# EFUSE_AND_REGULATOR.net
KiCad netlist of a schematic drawn in Altium Designer
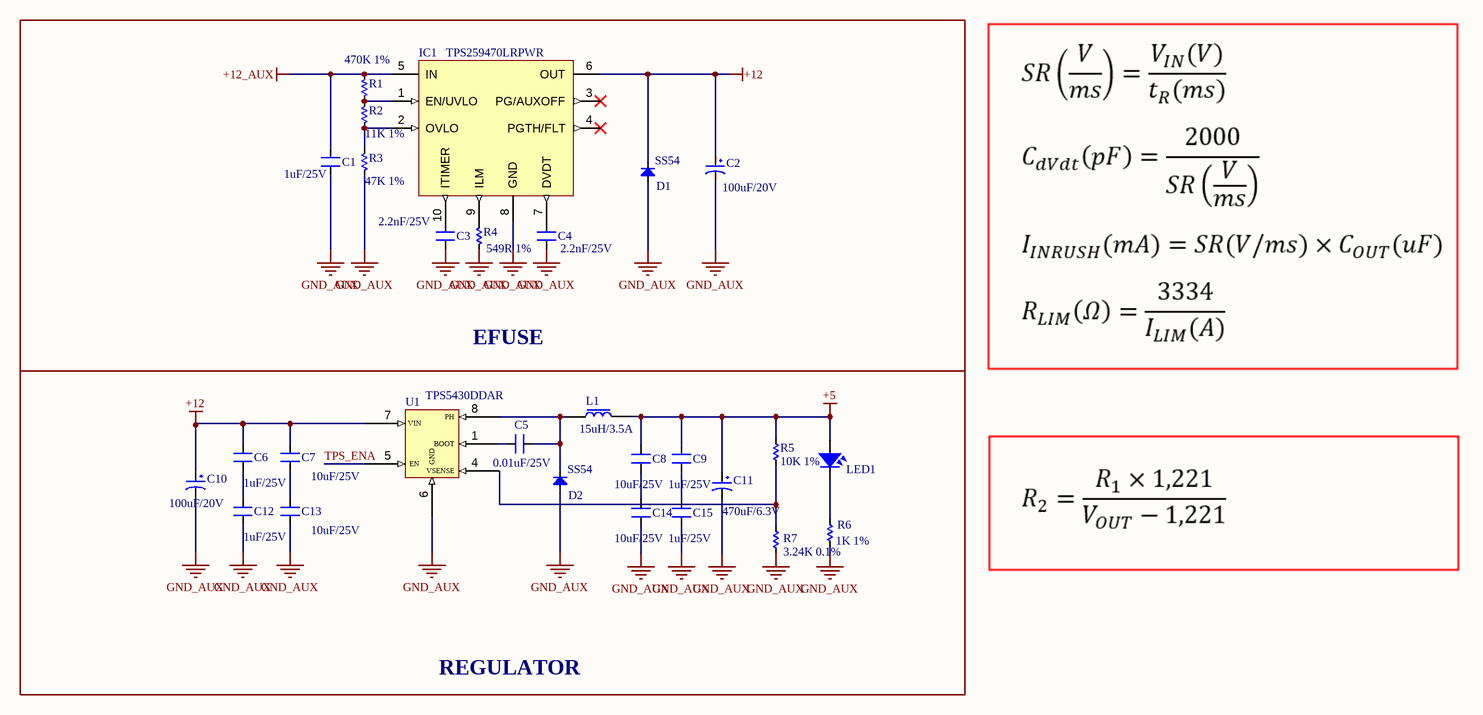
[diagram p0: EFUSE_AND_REGULATOR.SchDoc]

(export (version "E")
  (design (tool "Eeschema 10.0.6"))
  (components
    (comp (ref "C1")
      (value "1uF/25V")
      (footprint "SM-0603")
      (description "0603")
      (libsource (lib "Capacitors") (part "CM"))
    )
    (comp (ref "C2")
      (value "100uF/20V")
      (footprint "tu tantalum smd7343")
      (description "TAJD107K020RNJ")
      (libsource (lib "Altium_Lib_by_KhueNguyenCreator") (part "Tu tantalum 100uF 25V SMD7343"))
    )
    (comp (ref "C3")
      (value "2.2nF/25V")
      (footprint "SM-0603")
      (description "0603")
      (libsource (lib "Capacitors") (part "CM"))
    )
    (comp (ref "C4")
      (value "2.2nF/25V")
      (footprint "SM-0603")
      (description "0603")
      (libsource (lib "Capacitors") (part "CM"))
    )
    (comp (ref "C5")
      (value "0.01uF/25V")
      (footprint "SM-0603")
      (description "0603")
      (libsource (lib "Capacitors") (part "CM"))
    )
    (comp (ref "C6")
      (value "1uF/25V")
      (footprint "SM-0603")
      (description "0603")
      (libsource (lib "Capacitors") (part "CM"))
    )
    (comp (ref "C7")
      (value "10uF/25V")
      (footprint "SM-0603")
      (description "0603")
      (libsource (lib "Capacitors") (part "CM"))
    )
    (comp (ref "C8")
      (value "10uF/25V")
      (footprint "SM-0603")
      (description "0603")
      (libsource (lib "Capacitors") (part "CM"))
    )
    (comp (ref "C9")
      (value "1uF/25V")
      (footprint "SM-0603")
      (description "0603")
      (libsource (lib "Capacitors") (part "CM"))
    )
    (comp (ref "C10")
      (value "100uF/20V")
      (footprint "tu tantalum smd7343")
      (description "TAJD107K020RNJ")
      (libsource (lib "Altium_Lib_by_KhueNguyenCreator") (part "Tu tantalum 100uF 25V SMD7343"))
    )
    (comp (ref "C11")
      (value "470uF/6.3V")
      (footprint "tu tantalum smd7343")
      (description "TAJD477K006RNJ")
      (libsource (lib "Altium_Lib_by_KhueNguyenCreator") (part "Tu tantalum 100uF 25V SMD7343"))
    )
    (comp (ref "C12")
      (value "1uF/25V")
      (footprint "SM-0603")
      (description "0603")
      (libsource (lib "Capacitors") (part "CM"))
    )
    (comp (ref "C13")
      (value "10uF/25V")
      (footprint "SM-0603")
      (description "0603")
      (libsource (lib "Capacitors") (part "CM"))
    )
    (comp (ref "C14")
      (value "10uF/25V")
      (footprint "SM-0603")
      (description "0603")
      (libsource (lib "Capacitors") (part "CM"))
    )
    (comp (ref "C15")
      (value "1uF/25V")
      (footprint "SM-0603")
      (description "0603")
      (libsource (lib "Capacitors") (part "CM"))
    )
    (comp (ref "D1")
      (value "SS54")
      (footprint "DIO-SMD-A")
      (description "DIODE SCHOTTKY 40V 5A SMA")
      (fields (field (name "PUBLISHER") "Altium Limited"))
      (libsource (lib "Library") (part "Diode SMD"))
    )
    (comp (ref "D2")
      (value "SS54")
      (footprint "DIO-SMD-A")
      (description "DIODE SCHOTTKY 40V 5A SMA")
      (fields (field (name "PUBLISHER") "Altium Limited"))
      (libsource (lib "Library") (part "Diode SMD"))
    )
    (comp (ref "IC1")
      (value "TPS259470LRPWR")
      (footprint "TPS259470")
      (description "P/N: TPS259470LRPWR")
      (libsource (lib "Library") (part "TPS259470"))
    )
    (comp (ref "L1")
      (value "15uH/3.5A")
      (footprint "SRP7050TA")
      (description "SRP7050TA-150M")
      (libsource (lib "Library") (part "INDUCTOR"))
    )
    (comp (ref "LED1") (value "LED") (footprint "REDLED_0603") (libsource (lib "Library") (part "LED SMD")))
    (comp (ref "R1")
      (value "470K 1%")
      (footprint "RES-SMD-0603")
      (description "0603")
      (fields
        (field (name "MANUFACTURER") "Generic Components")
        (field (name "PUBLISHER") "Altium Hobart Technology Centre")
      )
      (libsource (lib "Library") (part "Res-SMD"))
    )
    (comp (ref "R2")
      (value "11K 1%")
      (footprint "RES-SMD-0603")
      (description "0603")
      (fields
        (field (name "MANUFACTURER") "Generic Components")
        (field (name "PUBLISHER") "Altium Hobart Technology Centre")
      )
      (libsource (lib "Library") (part "Res-SMD"))
    )
    (comp (ref "R3")
      (value "47K 1%")
      (footprint "RES-SMD-0603")
      (description "0603")
      (fields
        (field (name "MANUFACTURER") "Generic Components")
        (field (name "PUBLISHER") "Altium Hobart Technology Centre")
      )
      (libsource (lib "Library") (part "Res-SMD"))
    )
    (comp (ref "R4")
      (value "549R 1%")
      (footprint "RES-SMD-0603")
      (description "0603")
      (fields
        (field (name "MANUFACTURER") "Generic Components")
        (field (name "PUBLISHER") "Altium Hobart Technology Centre")
      )
      (libsource (lib "Library") (part "Res-SMD"))
    )
    (comp (ref "R5")
      (value "10K 1%")
      (footprint "RES-SMD-0603")
      (description "0603")
      (fields
        (field (name "MANUFACTURER") "Generic Components")
        (field (name "PUBLISHER") "Altium Hobart Technology Centre")
      )
      (libsource (lib "Library") (part "Res-SMD"))
    )
    (comp (ref "R6")
      (value "1K 1%")
      (footprint "RES-SMD-0603")
      (description "0603")
      (fields
        (field (name "MANUFACTURER") "Generic Components")
        (field (name "PUBLISHER") "Altium Hobart Technology Centre")
      )
      (libsource (lib "Library") (part "Res-SMD"))
    )
    (comp (ref "R7")
      (value "3.24K 0.1%")
      (footprint "RES-SMD-0603")
      (description "ERA-3AEB3241V")
      (fields
        (field (name "MANUFACTURER") "Generic Components")
        (field (name "PUBLISHER") "Altium Hobart Technology Centre")
      )
      (libsource (lib "Library") (part "Res-SMD"))
    )
    (comp (ref "U1")
      (value "TPS5430DDAR")
      (footprint "HSOP8")
      (description "8SOP")
      (libsource (lib "Library") (part "TPS543X"))
    )
  )
  (nets
    (net (code "1") (name "+5") (class "Default")
      (node (ref "C11") (pin "1") (pinfunction "1_1") (pintype "passive"))
      (node (ref "C8") (pin "1") (pinfunction "1_1") (pintype "passive"))
      (node (ref "C9") (pin "1") (pinfunction "1_1") (pintype "passive"))
      (node (ref "L1") (pin "2") (pintype "power_in"))
      (node (ref "LED1") (pin "1") (pinfunction "1_1") (pintype "passive"))
      (node (ref "R5") (pin "2") (pinfunction "2_2") (pintype "passive"))
    )
    (net (code "2") (name "+12") (class "Default")
      (node (ref "C10") (pin "1") (pinfunction "1_1") (pintype "passive"))
      (node (ref "C2") (pin "1") (pinfunction "1_1") (pintype "passive"))
      (node (ref "C6") (pin "1") (pinfunction "1_1") (pintype "passive"))
      (node (ref "C7") (pin "1") (pinfunction "1_1") (pintype "passive"))
      (node (ref "D1") (pin "2") (pinfunction "K_2") (pintype "passive"))
      (node (ref "IC1") (pin "6") (pinfunction "OUT_6") (pintype "power_in"))
      (node (ref "U1") (pin "7") (pinfunction "VIN_7") (pintype "input"))
    )
    (net (code "3") (name "+12_AUX") (class "Default")
      (node (ref "C1") (pin "2") (pinfunction "2_2") (pintype "passive"))
      (node (ref "IC1") (pin "5") (pinfunction "IN_5") (pintype "power_in"))
      (node (ref "R1") (pin "2") (pinfunction "2_2") (pintype "passive"))
    )
    (net (code "4") (name "/TPS_ENA") (class "Default")
      (node (ref "U1") (pin "5") (pinfunction "EN_5") (pintype "input"))
    )
    (net (code "5") (name "GND_AUX") (class "Default")
      (node (ref "C1") (pin "1") (pinfunction "1_1") (pintype "passive"))
      (node (ref "C10") (pin "2") (pinfunction "2_2") (pintype "passive"))
      (node (ref "C11") (pin "2") (pinfunction "2_2") (pintype "passive"))
      (node (ref "C12") (pin "2") (pinfunction "2_2") (pintype "passive"))
      (node (ref "C13") (pin "2") (pinfunction "2_2") (pintype "passive"))
      (node (ref "C14") (pin "2") (pinfunction "2_2") (pintype "passive"))
      (node (ref "C15") (pin "2") (pinfunction "2_2") (pintype "passive"))
      (node (ref "C2") (pin "2") (pinfunction "2_2") (pintype "passive"))
      (node (ref "C3") (pin "1") (pinfunction "1_1") (pintype "passive"))
      (node (ref "C4") (pin "1") (pinfunction "1_1") (pintype "passive"))
      (node (ref "D1") (pin "1") (pinfunction "A_1") (pintype "passive"))
      (node (ref "D2") (pin "1") (pinfunction "A_1") (pintype "passive"))
      (node (ref "IC1") (pin "8") (pinfunction "GND_8") (pintype "power_in"))
      (node (ref "R3") (pin "1") (pinfunction "1_1") (pintype "passive"))
      (node (ref "R4") (pin "1") (pinfunction "1_1") (pintype "passive"))
      (node (ref "R6") (pin "2") (pinfunction "2_2") (pintype "passive"))
      (node (ref "R7") (pin "1") (pinfunction "1_1") (pintype "passive"))
      (node (ref "U1") (pin "6") (pinfunction "GND_6") (pintype "input"))
    )
    (net (code "6") (name "Net-(C12-Pad1)") (class "Default")
      (node (ref "C12") (pin "1") (pinfunction "1_1") (pintype "passive"))
      (node (ref "C6") (pin "2") (pinfunction "2_2") (pintype "passive"))
    )
    (net (code "7") (name "Net-(C13-Pad1)") (class "Default")
      (node (ref "C13") (pin "1") (pinfunction "1_1") (pintype "passive"))
      (node (ref "C7") (pin "2") (pinfunction "2_2") (pintype "passive"))
    )
    (net (code "8") (name "Net-(C14-Pad1)") (class "Default")
      (node (ref "C14") (pin "1") (pinfunction "1_1") (pintype "passive"))
      (node (ref "C8") (pin "2") (pinfunction "2_2") (pintype "passive"))
    )
    (net (code "9") (name "Net-(C15-Pad1)") (class "Default")
      (node (ref "C15") (pin "1") (pinfunction "1_1") (pintype "passive"))
      (node (ref "C9") (pin "2") (pinfunction "2_2") (pintype "passive"))
    )
    (net (code "10") (name "Net-(D2-K)") (class "Default")
      (node (ref "C5") (pin "1") (pinfunction "1_1") (pintype "passive"))
      (node (ref "D2") (pin "2") (pinfunction "K_2") (pintype "passive"))
      (node (ref "L1") (pin "1") (pintype "power_in"))
      (node (ref "U1") (pin "8") (pinfunction "PH_8") (pintype "input"))
    )
    (net (code "11") (name "Net-(IC1-DVDT)") (class "Default")
      (node (ref "C4") (pin "2") (pinfunction "2_2") (pintype "passive"))
      (node (ref "IC1") (pin "7") (pinfunction "DVDT_7") (pintype "output"))
    )
    (net (code "12") (name "Net-(IC1-EN{slash}UVLO)") (class "Default")
      (node (ref "IC1") (pin "1") (pinfunction "EN/UVLO_1") (pintype "input"))
      (node (ref "R1") (pin "1") (pinfunction "1_1") (pintype "passive"))
      (node (ref "R2") (pin "2") (pinfunction "2_2") (pintype "passive"))
    )
    (net (code "13") (name "Net-(IC1-ILM)") (class "Default")
      (node (ref "IC1") (pin "9") (pinfunction "ILM_9") (pintype "output"))
      (node (ref "R4") (pin "2") (pinfunction "2_2") (pintype "passive"))
    )
    (net (code "14") (name "Net-(IC1-ITIMER)") (class "Default")
      (node (ref "C3") (pin "2") (pinfunction "2_2") (pintype "passive"))
      (node (ref "IC1") (pin "10") (pinfunction "ITIMER_10") (pintype "output"))
    )
    (net (code "15") (name "Net-(IC1-OVLO)") (class "Default")
      (node (ref "IC1") (pin "2") (pinfunction "OVLO_2") (pintype "input"))
      (node (ref "R2") (pin "1") (pinfunction "1_1") (pintype "passive"))
      (node (ref "R3") (pin "2") (pinfunction "2_2") (pintype "passive"))
    )
    (net (code "16") (name "Net-(LED1-Pad2)") (class "Default")
      (node (ref "LED1") (pin "2") (pinfunction "2_2") (pintype "passive"))
      (node (ref "R6") (pin "1") (pinfunction "1_1") (pintype "passive"))
    )
    (net (code "17") (name "Net-(U1-BOOT)") (class "Default")
      (node (ref "C5") (pin "2") (pinfunction "2_2") (pintype "passive"))
      (node (ref "U1") (pin "1") (pinfunction "BOOT_1") (pintype "input"))
    )
    (net (code "18") (name "Net-(U1-VSENSE)") (class "Default")
      (node (ref "R5") (pin "1") (pinfunction "1_1") (pintype "passive"))
      (node (ref "R7") (pin "2") (pinfunction "2_2") (pintype "passive"))
      (node (ref "U1") (pin "4") (pinfunction "VSENSE_4") (pintype "input"))
    )
    (net (code "19") (name "unconnected-(IC1-PGTH{slash}FLT-Pad4)") (class "Default")
      (node (ref "IC1") (pin "4") (pinfunction "PGTH/FLT_4") (pintype "output+no_connect"))
    )
    (net (code "20") (name "unconnected-(IC1-PG{slash}AUXOFF-Pad3)") (class "Default")
      (node (ref "IC1") (pin "3") (pinfunction "PG/AUXOFF_3") (pintype "output+no_connect"))
    )
  )
)
